# TriggerTrap.net
KiCad netlist of a schematic drawn in EAGLE
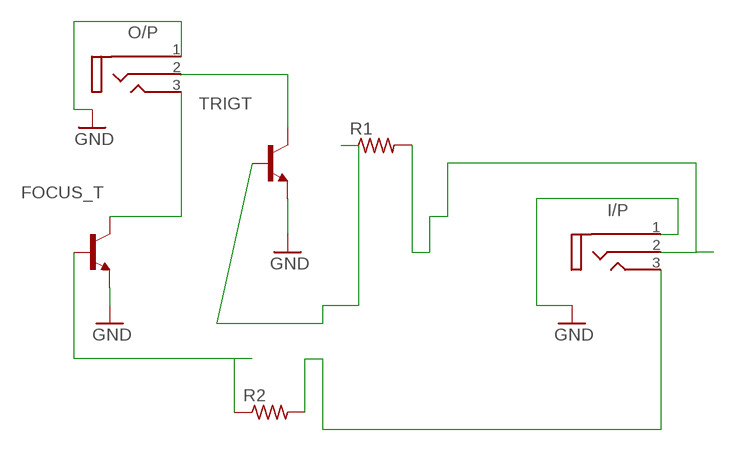
[diagram p0: schematic, sheet 1]

(export (version "E")
  (design (tool "Eeschema 10.0.6"))
  (components
    (comp (ref "FOCUS_T")
      (value "BC547")
      (footprint "eagle-import:TO92")
      (libsource (lib "eagle-import") (part "BC547"))
    )
    (comp (ref "I/P")
      (value "CON-3.5MM-STEREO-SMT")
      (footprint "eagle-import:CON-3.5MM-STEREO-SMT")
      (libsource (lib "eagle-import") (part "CON-3.5MM-STEREO-SMT"))
    )
    (comp (ref "O/P")
      (value "CON-3.5MM-STEREO-SMT")
      (footprint "eagle-import:CON-3.5MM-STEREO-SMT")
      (libsource (lib "eagle-import") (part "CON-3.5MM-STEREO-SMT"))
    )
    (comp (ref "R1")
      (value "R-US_FLIPFLOP7")
      (footprint "eagle-import:0805-THM-7")
      (libsource (lib "eagle-import") (part "R-US_FLIPFLOP7"))
    )
    (comp (ref "R2")
      (value "R-US_FLIPFLOP7")
      (footprint "eagle-import:0805-THM-7")
      (libsource (lib "eagle-import") (part "R-US_FLIPFLOP7"))
    )
    (comp (ref "TRIGT")
      (value "BC547")
      (footprint "eagle-import:TO92")
      (libsource (lib "eagle-import") (part "BC547"))
    )
  )
  (nets
    (net (code "1") (name "GND") (class "Default")
      (node (ref "FOCUS_T") (pin "1") (pinfunction "E_1") (pintype "passive"))
      (node (ref "I/P") (pin "1") (pinfunction "1_1") (pintype "bidirectional"))
      (node (ref "O/P") (pin "1") (pinfunction "1_1") (pintype "bidirectional"))
      (node (ref "TRIGT") (pin "1") (pinfunction "E_1") (pintype "passive"))
    )
    (net (code "2") (name "Net-(FOCUS_T-B)") (class "Default")
      (node (ref "FOCUS_T") (pin "2") (pinfunction "B_2") (pintype "passive"))
      (node (ref "R2") (pin "1") (pinfunction "1_1") (pintype "passive"))
    )
    (net (code "3") (name "Net-(FOCUS_T-C)") (class "Default")
      (node (ref "FOCUS_T") (pin "3") (pinfunction "C_3") (pintype "passive"))
      (node (ref "O/P") (pin "3") (pinfunction "3_3") (pintype "bidirectional"))
    )
    (net (code "4") (name "Net-(I/P-Pad2)") (class "Default")
      (node (ref "I/P") (pin "2") (pinfunction "2_2") (pintype "bidirectional"))
      (node (ref "R1") (pin "2") (pinfunction "2_2") (pintype "passive"))
    )
    (net (code "5") (name "Net-(I/P-Pad3)") (class "Default")
      (node (ref "I/P") (pin "3") (pinfunction "3_3") (pintype "bidirectional"))
      (node (ref "R2") (pin "2") (pinfunction "2_2") (pintype "passive"))
    )
    (net (code "6") (name "Net-(TRIGT-B)") (class "Default")
      (node (ref "R1") (pin "1") (pinfunction "1_1") (pintype "passive"))
      (node (ref "TRIGT") (pin "2") (pinfunction "B_2") (pintype "passive"))
    )
    (net (code "7") (name "Net-(TRIGT-C)") (class "Default")
      (node (ref "O/P") (pin "2") (pinfunction "2_2") (pintype "bidirectional"))
      (node (ref "TRIGT") (pin "3") (pinfunction "C_3") (pintype "passive"))
    )
  )
)
